# dribblerconn.net
KiCad netlist of a schematic drawn in Altium Designer
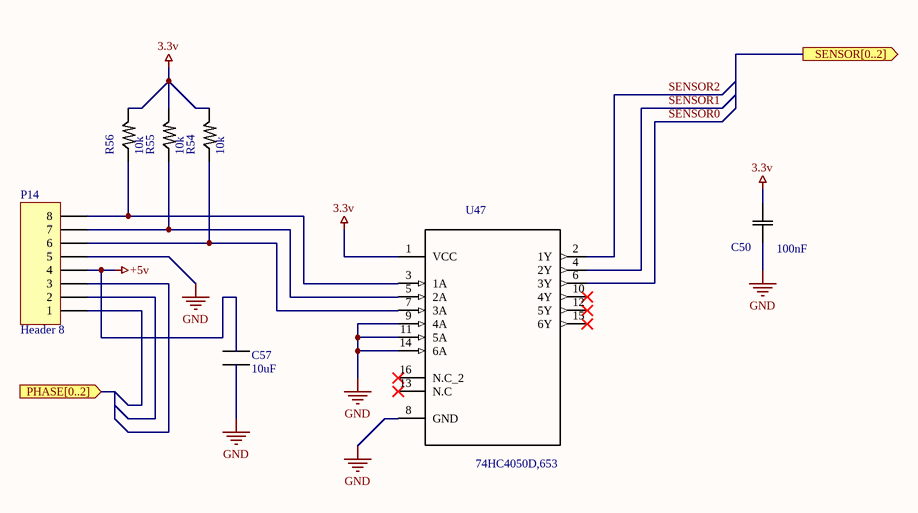
[diagram p0: dribblerconn.SchDoc]

(export (version "E")
  (design (tool "Eeschema 10.0.6"))
  (components
    (comp (ref "C50")
      (value "100nF")
      (footprint "CAPC2013X110N")
      (description "Capacitor; Ceramic; Cap; .100UF ; Tol+-10%; SMD; Vol-Rtg 50V; X7R, Tape/Reel")
      (fields (field (name "MP") "C0805C104K5RACTU") (field (name "MF") "Kemet"))
      (libsource (lib "100nF-C0805C104K5RACTU") (part "C0805C104K5RACTU"))
    )
    (comp (ref "C57")
      (value "10uF")
      (footprint "CAPC3216X100N")
      (libsource (lib "10uFCAPC3216X100N") (part "Component_1"))
    )
    (comp (ref "P14")
      (value "Header 8")
      (footprint "HDR1X8")
      (description "Header, 8-Pin")
      (fields (field (name "PUBLISHER") "Altium Limited"))
      (libsource (lib "Miscellaneous Connectors") (part "Header 8"))
    )
    (comp (ref "R54")
      (value "10k")
      (footprint "RESC2012X60")
      (description "RES SMD 10K OHM 1% 1/8W 0805")
      (fields (field (name "MP") "RC0805FR-0710KL") (field (name "MF") "Yageo"))
      (libsource (lib "10KOhm") (part "RC0805FR-0710KL"))
    )
    (comp (ref "R55")
      (value "10k")
      (footprint "RESC2012X60")
      (description "RES SMD 10K OHM 1% 1/8W 0805")
      (fields (field (name "MP") "RC0805FR-0710KL") (field (name "MF") "Yageo"))
      (libsource (lib "10KOhm") (part "RC0805FR-0710KL"))
    )
    (comp (ref "R56")
      (value "10k")
      (footprint "RESC2012X60")
      (description "RES SMD 10K OHM 1% 1/8W 0805")
      (fields (field (name "MP") "RC0805FR-0710KL") (field (name "MF") "Yageo"))
      (libsource (lib "10KOhm") (part "RC0805FR-0710KL"))
    )
    (comp (ref "U47")
      (value "74HC4050D,653")
      (footprint "SOIC127P600X175-16N")
      (description "74HC Series 6 V Surface Mount Hex High-to-Low Level Shifter - SOIC-16")
      (fields (field (name "MF") "Nexperia") (field (name "DIGI-KEY_PART_NUMBER") "1727-6331-1-ND"))
      (libsource (lib "74HC4050D_653") (part "74HC4050D,653"))
    )
  )
  (nets
    (net (code "4") (name "+5v") (class "Default")
      (node (ref "C57") (pin "Out") (pinfunction "Out_Out") (pintype "passive"))
      (node (ref "P14") (pin "4") (pinfunction "4_4") (pintype "passive"))
    )
    (net (code "6") (name "/SENSOR0") (class "Default")
      (node (ref "U47") (pin "6") (pinfunction "3Y_6") (pintype "output"))
    )
    (net (code "7") (name "/SENSOR1") (class "Default")
      (node (ref "U47") (pin "4") (pinfunction "2Y_4") (pintype "output"))
    )
    (net (code "8") (name "/SENSOR2") (class "Default")
      (node (ref "U47") (pin "2") (pinfunction "1Y_2") (pintype "output"))
    )
    (net (code "10") (name "3.3v") (class "Default")
      (node (ref "C50") (pin "2") (pinfunction "C2_2") (pintype "passive"))
      (node (ref "R54") (pin "2") (pinfunction "2_2") (pintype "passive"))
      (node (ref "R55") (pin "2") (pinfunction "2_2") (pintype "passive"))
      (node (ref "R56") (pin "2") (pinfunction "2_2") (pintype "passive"))
      (node (ref "U47") (pin "1") (pinfunction "VCC_1") (pintype "power_in"))
    )
    (net (code "11") (name "GND") (class "Default")
      (node (ref "C50") (pin "1") (pinfunction "C1_1") (pintype "passive"))
      (node (ref "C57") (pin "In") (pinfunction "In_In") (pintype "passive"))
      (node (ref "P14") (pin "5") (pinfunction "5_5") (pintype "passive"))
      (node (ref "U47") (pin "11") (pinfunction "5A_11") (pintype "input"))
      (node (ref "U47") (pin "14") (pinfunction "6A_14") (pintype "input"))
      (node (ref "U47") (pin "8") (pinfunction "GND_8") (pintype "passive"))
      (node (ref "U47") (pin "9") (pinfunction "4A_9") (pintype "input"))
    )
    (net (code "12") (name "Net-(U47-1A)") (class "Default")
      (node (ref "P14") (pin "8") (pinfunction "8_8") (pintype "passive"))
      (node (ref "R56") (pin "1") (pinfunction "1_1") (pintype "passive"))
      (node (ref "U47") (pin "3") (pinfunction "1A_3") (pintype "input"))
    )
    (net (code "13") (name "Net-(U47-2A)") (class "Default")
      (node (ref "P14") (pin "7") (pinfunction "7_7") (pintype "passive"))
      (node (ref "R55") (pin "1") (pinfunction "1_1") (pintype "passive"))
      (node (ref "U47") (pin "5") (pinfunction "2A_5") (pintype "input"))
    )
    (net (code "14") (name "Net-(U47-3A)") (class "Default")
      (node (ref "P14") (pin "6") (pinfunction "6_6") (pintype "passive"))
      (node (ref "R54") (pin "1") (pinfunction "1_1") (pintype "passive"))
      (node (ref "U47") (pin "7") (pinfunction "3A_7") (pintype "input"))
    )
    (net (code "15") (name "unconnected-(P14-Pad1)") (class "Default")
      (node (ref "P14") (pin "1") (pinfunction "1_1") (pintype "passive"))
    )
    (net (code "16") (name "unconnected-(P14-Pad2)") (class "Default")
      (node (ref "P14") (pin "2") (pinfunction "2_2") (pintype "passive"))
    )
    (net (code "17") (name "unconnected-(P14-Pad3)") (class "Default")
      (node (ref "P14") (pin "3") (pinfunction "3_3") (pintype "passive"))
    )
    (net (code "18") (name "unconnected-(U47-4Y-Pad10)") (class "Default")
      (node (ref "U47") (pin "10") (pinfunction "4Y_10") (pintype "output+no_connect"))
    )
    (net (code "19") (name "unconnected-(U47-5Y-Pad12)") (class "Default")
      (node (ref "U47") (pin "12") (pinfunction "5Y_12") (pintype "output+no_connect"))
    )
    (net (code "20") (name "unconnected-(U47-6Y-Pad15)") (class "Default")
      (node (ref "U47") (pin "15") (pinfunction "6Y_15") (pintype "output+no_connect"))
    )
    (net (code "21") (name "unconnected-(U47-N.C-Pad13)") (class "Default")
      (node (ref "U47") (pin "13") (pinfunction "N.C_13") (pintype "passive+no_connect"))
    )
    (net (code "22") (name "unconnected-(U47-N.C_2-Pad16)") (class "Default")
      (node (ref "U47") (pin "16") (pinfunction "N.C_2_16") (pintype "passive+no_connect"))
    )
  )
)
